# soldeerboutmainbody2.net
KiCad netlist of a schematic drawn in Altium Designer
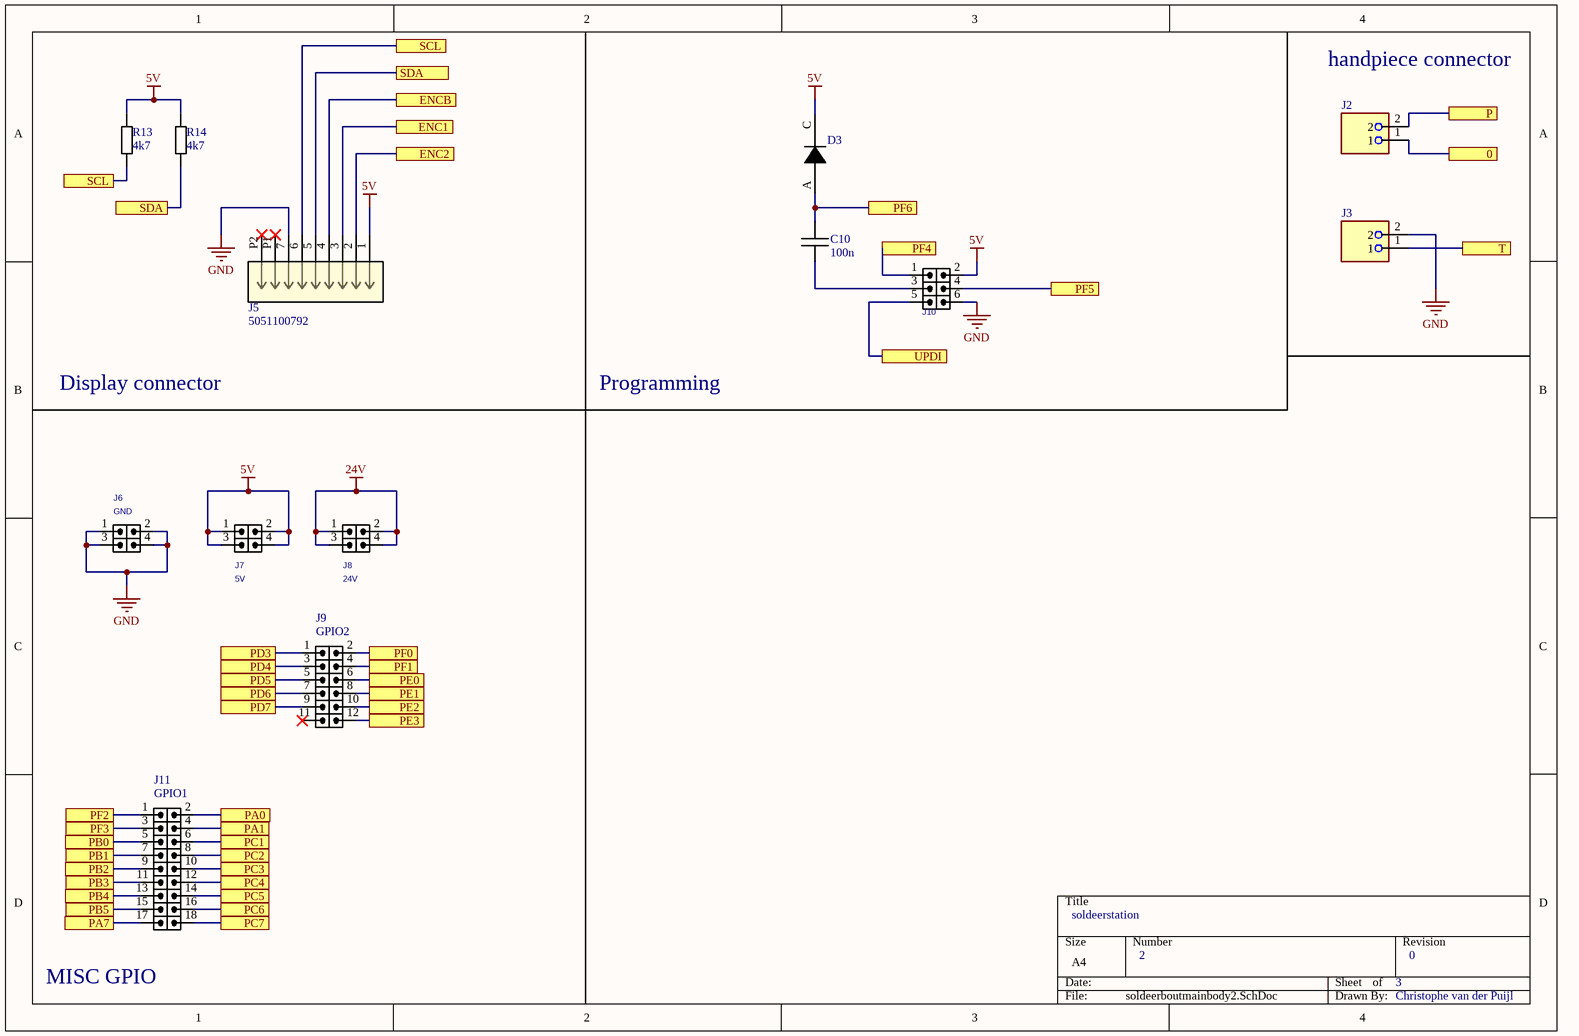
[diagram p0: soldeerboutmainbody2.SchDoc]

(export (version "E")
  (design (tool "Eeschema 10.0.6"))
  (components
    (comp (ref "C10")
      (value "100n")
      (footprint "C 0603 / 1608")
      (libsource (lib "Standard") (part "Capacitor"))
    )
    (comp (ref "D3")
      (value "1N4148WX-TP")
      (footprint "SOD2512X115N")
      (fields (field (name "MF") "{'manufacturer': u'Micro Commercial'}"))
      (libsource (lib "Standard") (part "1N4148WX-TP"))
    )
    (comp (ref "J2")
      (value "1935161")
      (footprint "PHOENIX_1935161")
      (fields (field (name "MF") "{'manufacturer': u'Phoenix Contact'}"))
      (libsource (lib "Standard") (part "1935161"))
    )
    (comp (ref "J3")
      (value "1935161")
      (footprint "PHOENIX_1935161")
      (fields (field (name "MF") "{'manufacturer': u'Phoenix Contact'}"))
      (libsource (lib "Standard") (part "1935161"))
    )
    (comp (ref "J5")
      (value "5051100792")
      (footprint "CON_5051100792_MOL")
      (description "No Description Available")
      (libsource (lib "Standard") (part "5051100792"))
    )
    (comp (ref "J6")
      (value "GND")
      (footprint "HDR2_M_2X2")
      (description "CONN, HEADER, Male, pitch: 2.54mm, 4POS")
      (fields (field (name "MANF_P#") "MANF_PART#") (field (name "MANF") "MANF"))
      (libsource (lib "Standard") (part "HDRRS_M_2X2"))
    )
    (comp (ref "J7")
      (value "5V")
      (footprint "HDR2_M_2X2")
      (description "CONN, HEADER, Male, pitch: 2.54mm, 4POS")
      (fields (field (name "MANF_P#") "MANF_PART#") (field (name "MANF") "MANF"))
      (libsource (lib "Standard") (part "HDRRS_M_2X2"))
    )
    (comp (ref "J8")
      (value "24V")
      (footprint "HDR2_M_2X2")
      (description "CONN, HEADER, Male, pitch: 2.54mm, 4POS")
      (fields (field (name "MANF_P#") "MANF_PART#") (field (name "MANF") "MANF"))
      (libsource (lib "Standard") (part "HDRRS_M_2X2"))
    )
    (comp (ref "J9")
      (value "GPIO2")
      (footprint "HDR2_M_2X6")
      (description "CONN, HEADER, Male, pitch: 2.54mm, 12POS")
      (libsource (lib "Standard") (part "HDRRS_M_2X6"))
    )
    (comp (ref "J10")
      (value "HDRM_2X3")
      (footprint "HDR2_M_2X3")
      (description "CONN, HEADER, Male, pitch: 2.54mm, 6POS")
      (fields (field (name "MANF_P#") "MANF_PART#") (field (name "MANF") "MANF"))
      (libsource (lib "Standard") (part "HDRRS_M_2X3"))
    )
    (comp (ref "J11")
      (value "GPIO1")
      (footprint "HDR2_M_2X9")
      (description "CONN, HEADER, Male, pitch: 2.54mm, 18POS")
      (libsource (lib "Standard") (part "HDRRS_M_2X9"))
    )
    (comp (ref "R13") (value "4k7") (footprint "R 0603") (libsource (lib "Standard") (part "Resistor")))
    (comp (ref "R14") (value "4k7") (footprint "R 0603") (libsource (lib "Standard") (part "Resistor")))
  )
  (nets
    (net (code "1") (name "/0") (class "Default")
      (node (ref "J2") (pin "1") (pinfunction "1_1") (pintype "passive"))
    )
    (net (code "2") (name "/ENC1") (class "Default")
      (node (ref "J5") (pin "3") (pinfunction "3_3") (pintype "passive"))
    )
    (net (code "3") (name "/ENC2") (class "Default")
      (node (ref "J5") (pin "2") (pinfunction "2_2") (pintype "passive"))
    )
    (net (code "4") (name "/ENCB") (class "Default")
      (node (ref "J5") (pin "4") (pinfunction "4_4") (pintype "passive"))
    )
    (net (code "5") (name "/P") (class "Default")
      (node (ref "J2") (pin "2") (pinfunction "2_2") (pintype "passive"))
    )
    (net (code "6") (name "/PA0") (class "Default")
      (node (ref "J11") (pin "2") (pinfunction "2_2") (pintype "passive"))
    )
    (net (code "7") (name "/PA1") (class "Default")
      (node (ref "J11") (pin "4") (pinfunction "4_4") (pintype "passive"))
    )
    (net (code "8") (name "/PA7") (class "Default")
      (node (ref "J11") (pin "17") (pinfunction "17_17") (pintype "passive"))
    )
    (net (code "9") (name "/PB0") (class "Default")
      (node (ref "J11") (pin "5") (pinfunction "5_5") (pintype "passive"))
    )
    (net (code "10") (name "/PB1") (class "Default")
      (node (ref "J11") (pin "7") (pinfunction "7_7") (pintype "passive"))
    )
    (net (code "11") (name "/PB2") (class "Default")
      (node (ref "J11") (pin "9") (pinfunction "9_9") (pintype "passive"))
    )
    (net (code "12") (name "/PB3") (class "Default")
      (node (ref "J11") (pin "11") (pinfunction "11_11") (pintype "passive"))
    )
    (net (code "13") (name "/PB4") (class "Default")
      (node (ref "J11") (pin "13") (pinfunction "13_13") (pintype "passive"))
    )
    (net (code "14") (name "/PB5") (class "Default")
      (node (ref "J11") (pin "15") (pinfunction "15_15") (pintype "passive"))
    )
    (net (code "15") (name "/PC1") (class "Default")
      (node (ref "J11") (pin "6") (pinfunction "6_6") (pintype "passive"))
    )
    (net (code "16") (name "/PC2") (class "Default")
      (node (ref "J11") (pin "8") (pinfunction "8_8") (pintype "passive"))
    )
    (net (code "17") (name "/PC3") (class "Default")
      (node (ref "J11") (pin "10") (pinfunction "10_10") (pintype "passive"))
    )
    (net (code "18") (name "/PC4") (class "Default")
      (node (ref "J11") (pin "12") (pinfunction "12_12") (pintype "passive"))
    )
    (net (code "19") (name "/PC5") (class "Default")
      (node (ref "J11") (pin "14") (pinfunction "14_14") (pintype "passive"))
    )
    (net (code "20") (name "/PC6") (class "Default")
      (node (ref "J11") (pin "16") (pinfunction "16_16") (pintype "passive"))
    )
    (net (code "21") (name "/PC7") (class "Default")
      (node (ref "J11") (pin "18") (pinfunction "18_18") (pintype "passive"))
    )
    (net (code "22") (name "/PD3") (class "Default")
      (node (ref "J9") (pin "1") (pinfunction "1_1") (pintype "passive"))
    )
    (net (code "23") (name "/PD4") (class "Default")
      (node (ref "J9") (pin "3") (pinfunction "3_3") (pintype "passive"))
    )
    (net (code "24") (name "/PD5") (class "Default")
      (node (ref "J9") (pin "5") (pinfunction "5_5") (pintype "passive"))
    )
    (net (code "25") (name "/PD6") (class "Default")
      (node (ref "J9") (pin "7") (pinfunction "7_7") (pintype "passive"))
    )
    (net (code "26") (name "/PD7") (class "Default")
      (node (ref "J9") (pin "9") (pinfunction "9_9") (pintype "passive"))
    )
    (net (code "27") (name "/PE0") (class "Default")
      (node (ref "J9") (pin "6") (pinfunction "6_6") (pintype "passive"))
    )
    (net (code "28") (name "/PE1") (class "Default")
      (node (ref "J9") (pin "8") (pinfunction "8_8") (pintype "passive"))
    )
    (net (code "29") (name "/PE2") (class "Default")
      (node (ref "J9") (pin "10") (pinfunction "10_10") (pintype "passive"))
    )
    (net (code "30") (name "/PE3") (class "Default")
      (node (ref "J9") (pin "12") (pinfunction "12_12") (pintype "passive"))
    )
    (net (code "31") (name "/PF0") (class "Default")
      (node (ref "J9") (pin "2") (pinfunction "2_2") (pintype "passive"))
    )
    (net (code "32") (name "/PF1") (class "Default")
      (node (ref "J9") (pin "4") (pinfunction "4_4") (pintype "passive"))
    )
    (net (code "33") (name "/PF2") (class "Default")
      (node (ref "J11") (pin "1") (pinfunction "1_1") (pintype "passive"))
    )
    (net (code "34") (name "/PF3") (class "Default")
      (node (ref "J11") (pin "3") (pinfunction "3_3") (pintype "passive"))
    )
    (net (code "35") (name "/PF4") (class "Default")
      (node (ref "J10") (pin "1") (pinfunction "1_1") (pintype "passive"))
    )
    (net (code "36") (name "/PF5") (class "Default")
      (node (ref "J10") (pin "4") (pinfunction "4_4") (pintype "passive"))
    )
    (net (code "37") (name "/PF6") (class "Default")
      (node (ref "C10") (pin "1") (pinfunction "1_1") (pintype "passive"))
      (node (ref "D3") (pin "A") (pinfunction "ANODE_A") (pintype "passive"))
    )
    (net (code "38") (name "/SCL") (class "Default")
      (node (ref "J5") (pin "6") (pinfunction "6_6") (pintype "passive"))
      (node (ref "R13") (pin "1") (pinfunction "1_1") (pintype "passive"))
    )
    (net (code "39") (name "/SDA") (class "Default")
      (node (ref "J5") (pin "5") (pinfunction "5_5") (pintype "passive"))
      (node (ref "R14") (pin "1") (pinfunction "1_1") (pintype "passive"))
    )
    (net (code "40") (name "/T") (class "Default")
      (node (ref "J3") (pin "1") (pinfunction "1_1") (pintype "passive"))
    )
    (net (code "41") (name "/UPDI") (class "Default")
      (node (ref "J10") (pin "5") (pinfunction "5_5") (pintype "passive"))
    )
    (net (code "42") (name "5V") (class "Default")
      (node (ref "D3") (pin "C") (pinfunction "CATHODE_C") (pintype "passive"))
      (node (ref "J10") (pin "2") (pinfunction "2_2") (pintype "passive"))
      (node (ref "J5") (pin "1") (pinfunction "1_1") (pintype "passive"))
      (node (ref "J7") (pin "1") (pinfunction "1_1") (pintype "passive"))
      (node (ref "J7") (pin "2") (pinfunction "2_2") (pintype "passive"))
      (node (ref "J7") (pin "3") (pinfunction "3_3") (pintype "passive"))
      (node (ref "J7") (pin "4") (pinfunction "4_4") (pintype "passive"))
      (node (ref "R13") (pin "2") (pinfunction "2_2") (pintype "passive"))
      (node (ref "R14") (pin "2") (pinfunction "2_2") (pintype "passive"))
    )
    (net (code "43") (name "24V") (class "Default")
      (node (ref "J8") (pin "1") (pinfunction "1_1") (pintype "passive"))
      (node (ref "J8") (pin "2") (pinfunction "2_2") (pintype "passive"))
      (node (ref "J8") (pin "3") (pinfunction "3_3") (pintype "passive"))
      (node (ref "J8") (pin "4") (pinfunction "4_4") (pintype "passive"))
    )
    (net (code "44") (name "GND") (class "Default")
      (node (ref "J10") (pin "6") (pinfunction "6_6") (pintype "passive"))
      (node (ref "J3") (pin "2") (pinfunction "2_2") (pintype "passive"))
      (node (ref "J5") (pin "7") (pinfunction "7_7") (pintype "passive"))
      (node (ref "J6") (pin "1") (pinfunction "1_1") (pintype "passive"))
      (node (ref "J6") (pin "2") (pinfunction "2_2") (pintype "passive"))
      (node (ref "J6") (pin "3") (pinfunction "3_3") (pintype "passive"))
      (node (ref "J6") (pin "4") (pinfunction "4_4") (pintype "passive"))
    )
    (net (code "45") (name "Net-(C10-1-Pad2)") (class "Default")
      (node (ref "C10") (pin "2") (pinfunction "1_2") (pintype "passive"))
      (node (ref "J10") (pin "3") (pinfunction "3_3") (pintype "passive"))
    )
    (net (code "46") (name "unconnected-(J5-PadP1)") (class "Default")
      (node (ref "J5") (pin "P1") (pinfunction "P1_P1") (pintype "passive+no_connect"))
    )
    (net (code "47") (name "unconnected-(J5-PadP2)") (class "Default")
      (node (ref "J5") (pin "P2") (pinfunction "P2_P2") (pintype "passive+no_connect"))
    )
    (net (code "48") (name "unconnected-(J9-Pad11)") (class "Default")
      (node (ref "J9") (pin "11") (pinfunction "11_11") (pintype "passive+no_connect"))
    )
  )
)
